# StepperDriver.net
KiCad netlist of a schematic drawn in EAGLE
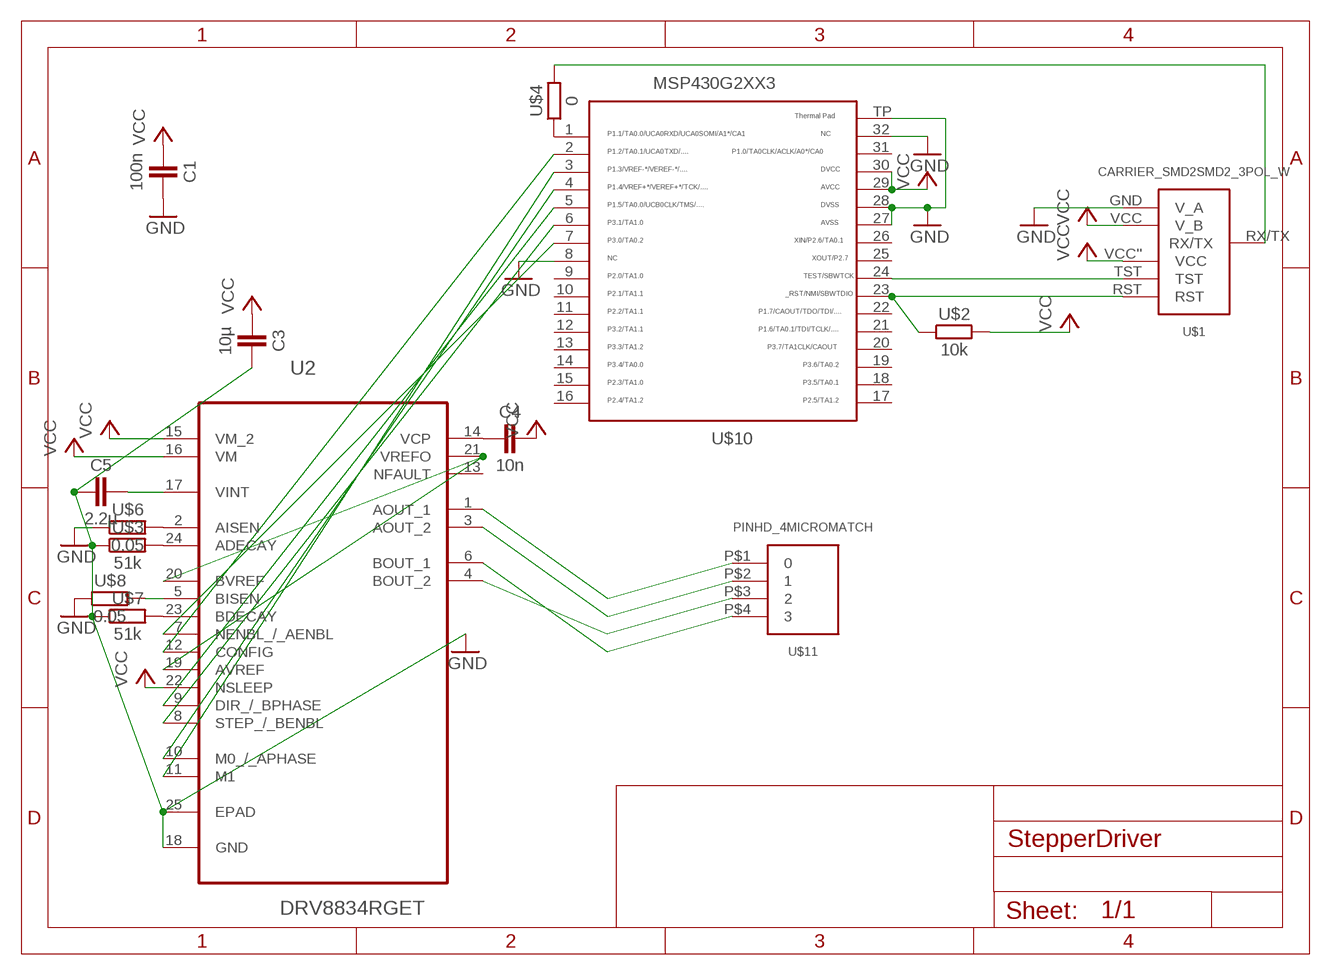
[diagram p0: schematic, sheet 1]

(export (version "E")
  (design (tool "Eeschema 10.0.6"))
  (components
    (comp (ref "C1")
      (value "100n")
      (footprint "eagle-import:603")
      (libsource (lib "eagle-import") (part "CAPACITOR"))
    )
    (comp (ref "C3")
      (value "10µ")
      (footprint "eagle-import:603")
      (libsource (lib "eagle-import") (part "CAPACITOR"))
    )
    (comp (ref "C4")
      (value "10n")
      (footprint "eagle-import:603")
      (libsource (lib "eagle-import") (part "CAPACITOR"))
    )
    (comp (ref "C5")
      (value "2.2µ")
      (footprint "eagle-import:603")
      (libsource (lib "eagle-import") (part "CAPACITOR"))
    )
    (comp (ref "U$1")
      (value "CARRIER_SMD2SMD2_3POL_W")
      (footprint "eagle-import:CARRIER_SMD2_WIDE_3POL")
      (libsource (lib "eagle-import") (part "CARRIER_SMD2SMD2_3POL_W"))
    )
    (comp (ref "U$2")
      (value "10k")
      (footprint "eagle-import:603")
      (libsource (lib "eagle-import") (part "RESISTOR0603"))
    )
    (comp (ref "U$3")
      (value "51k")
      (footprint "eagle-import:603")
      (libsource (lib "eagle-import") (part "RESISTOR0603"))
    )
    (comp (ref "U$4")
      (value "0")
      (footprint "eagle-import:603")
      (libsource (lib "eagle-import") (part "RESISTOR0603"))
    )
    (comp (ref "U$6")
      (value "0.05")
      (footprint "eagle-import:603")
      (libsource (lib "eagle-import") (part "RESISTOR0603"))
    )
    (comp (ref "U$7")
      (value "51k")
      (footprint "eagle-import:603")
      (libsource (lib "eagle-import") (part "RESISTOR0603"))
    )
    (comp (ref "U$8")
      (value "0.05")
      (footprint "eagle-import:603")
      (libsource (lib "eagle-import") (part "RESISTOR0603"))
    )
    (comp (ref "U$10")
      (value "MSP430G2553")
      (footprint "eagle-import:QFN32")
      (libsource (lib "eagle-import") (part "MSP430G2553"))
    )
    (comp (ref "U$11")
      (value "PINHD_4MICROMATCH")
      (footprint "eagle-import:MICROMATCH4P0L")
      (libsource (lib "eagle-import") (part "PINHD_4MICROMATCH"))
    )
    (comp (ref "U2")
      (value "DRV8834RGET")
      (footprint "eagle-import:QFN50P400X400X100-25N")
      (libsource (lib "eagle-import") (part "DRV8834RGET"))
    )
  )
  (nets
    (net (code "1") (name "GND") (class "Default")
      (node (ref "C1") (pin "2") (pinfunction "2_2") (pintype "passive"))
      (node (ref "C3") (pin "2") (pinfunction "2_2") (pintype "passive"))
      (node (ref "C5") (pin "1") (pinfunction "1_1") (pintype "passive"))
      (node (ref "U$1") (pin "GND") (pinfunction "V_A_GND") (pintype "bidirectional"))
      (node (ref "U$10") (pin "27") (pinfunction "27_27") (pintype "bidirectional"))
      (node (ref "U$10") (pin "28") (pinfunction "28_28") (pintype "bidirectional"))
      (node (ref "U$10") (pin "32") (pinfunction "32_32") (pintype "bidirectional"))
      (node (ref "U$10") (pin "8") (pinfunction "8_8") (pintype "bidirectional"))
      (node (ref "U$10") (pin "TP") (pinfunction "TP_TP") (pintype "bidirectional"))
      (node (ref "U$3") (pin "1") (pinfunction "1_1") (pintype "passive"))
      (node (ref "U$6") (pin "1") (pinfunction "1_1") (pintype "passive"))
      (node (ref "U$7") (pin "1") (pinfunction "1_1") (pintype "passive"))
      (node (ref "U$8") (pin "1") (pinfunction "1_1") (pintype "passive"))
      (node (ref "U2") (pin "18") (pinfunction "GND_18") (pintype "passive"))
      (node (ref "U2") (pin "25") (pinfunction "EPAD_25") (pintype "passive"))
    )
    (net (code "2") (name "Net-(U$1-PadRST)") (class "Default")
      (node (ref "U$1") (pin "RST") (pinfunction "RST_RST") (pintype "bidirectional"))
      (node (ref "U$10") (pin "23") (pinfunction "23_23") (pintype "bidirectional"))
      (node (ref "U$2") (pin "1") (pinfunction "1_1") (pintype "passive"))
    )
    (net (code "3") (name "Net-(U$1-PadRX{slash}TX)") (class "Default")
      (node (ref "U$1") (pin "RX/TX") (pinfunction "RX/TX_RX/TX") (pintype "bidirectional"))
      (node (ref "U$4") (pin "2") (pinfunction "2_2") (pintype "passive"))
    )
    (net (code "4") (name "Net-(U$1-PadTST)") (class "Default")
      (node (ref "U$1") (pin "TST") (pinfunction "TST_TST") (pintype "bidirectional"))
      (node (ref "U$10") (pin "24") (pinfunction "24_24") (pintype "bidirectional"))
    )
    (net (code "5") (name "Net-(U$10-Pad1)") (class "Default")
      (node (ref "U$10") (pin "1") (pinfunction "1_1") (pintype "bidirectional"))
      (node (ref "U$4") (pin "1") (pinfunction "1_1") (pintype "passive"))
    )
    (net (code "6") (name "Net-(U$11-0)") (class "Default")
      (node (ref "U$11") (pin "P$1") (pinfunction "0_P$1") (pintype "bidirectional"))
      (node (ref "U2") (pin "1") (pinfunction "AOUT_1_1") (pintype "output"))
    )
    (net (code "7") (name "Net-(U$11-1)") (class "Default")
      (node (ref "U$11") (pin "P$2") (pinfunction "1_P$2") (pintype "bidirectional"))
      (node (ref "U2") (pin "3") (pinfunction "AOUT_2_3") (pintype "output"))
    )
    (net (code "8") (name "Net-(U$11-2)") (class "Default")
      (node (ref "U$11") (pin "P$3") (pinfunction "2_P$3") (pintype "bidirectional"))
      (node (ref "U2") (pin "4") (pinfunction "BOUT_2_4") (pintype "output"))
    )
    (net (code "9") (name "Net-(U$11-3)") (class "Default")
      (node (ref "U$11") (pin "P$4") (pinfunction "3_P$4") (pintype "bidirectional"))
      (node (ref "U2") (pin "6") (pinfunction "BOUT_1_6") (pintype "output"))
    )
    (net (code "10") (name "Net-(U2-ADECAY)") (class "Default")
      (node (ref "U$3") (pin "2") (pinfunction "2_2") (pintype "passive"))
      (node (ref "U2") (pin "24") (pinfunction "ADECAY_24") (pintype "input"))
    )
    (net (code "11") (name "Net-(U2-AISEN)") (class "Default")
      (node (ref "U$6") (pin "2") (pinfunction "2_2") (pintype "passive"))
      (node (ref "U2") (pin "2") (pinfunction "AISEN_2") (pintype "bidirectional"))
    )
    (net (code "12") (name "Net-(U2-AVREF)") (class "Default")
      (node (ref "U2") (pin "19") (pinfunction "AVREF_19") (pintype "input"))
      (node (ref "U2") (pin "20") (pinfunction "BVREF_20") (pintype "input"))
      (node (ref "U2") (pin "21") (pinfunction "VREFO_21") (pintype "output"))
    )
    (net (code "13") (name "Net-(U2-BDECAY)") (class "Default")
      (node (ref "U$7") (pin "2") (pinfunction "2_2") (pintype "passive"))
      (node (ref "U2") (pin "23") (pinfunction "BDECAY_23") (pintype "input"))
    )
    (net (code "14") (name "Net-(U2-BISEN)") (class "Default")
      (node (ref "U$8") (pin "2") (pinfunction "2_2") (pintype "passive"))
      (node (ref "U2") (pin "5") (pinfunction "BISEN_5") (pintype "bidirectional"))
    )
    (net (code "15") (name "Net-(U2-CONFIG)") (class "Default")
      (node (ref "U$10") (pin "2") (pinfunction "2_2") (pintype "bidirectional"))
      (node (ref "U2") (pin "12") (pinfunction "CONFIG_12") (pintype "input"))
    )
    (net (code "16") (name "Net-(U2-DIR_{slash}_BPHASE)") (class "Default")
      (node (ref "U$10") (pin "5") (pinfunction "5_5") (pintype "bidirectional"))
      (node (ref "U2") (pin "9") (pinfunction "DIR_/_BPHASE_9") (pintype "input"))
    )
    (net (code "17") (name "Net-(U2-M0_{slash}_APHASE)") (class "Default")
      (node (ref "U$10") (pin "4") (pinfunction "4_4") (pintype "bidirectional"))
      (node (ref "U2") (pin "10") (pinfunction "M0_/_APHASE_10") (pintype "input"))
    )
    (net (code "18") (name "Net-(U2-M1)") (class "Default")
      (node (ref "U$10") (pin "3") (pinfunction "3_3") (pintype "bidirectional"))
      (node (ref "U2") (pin "11") (pinfunction "M1_11") (pintype "input"))
    )
    (net (code "19") (name "Net-(U2-NENBL_{slash}_AENBL)") (class "Default")
      (node (ref "U$10") (pin "7") (pinfunction "7_7") (pintype "bidirectional"))
      (node (ref "U2") (pin "7") (pinfunction "NENBL_/_AENBL_7") (pintype "input"))
    )
    (net (code "20") (name "Net-(U2-STEP_{slash}_BENBL)") (class "Default")
      (node (ref "U$10") (pin "6") (pinfunction "6_6") (pintype "bidirectional"))
      (node (ref "U2") (pin "8") (pinfunction "STEP_/_BENBL_8") (pintype "input"))
    )
    (net (code "21") (name "Net-(U2-VCP)") (class "Default")
      (node (ref "C4") (pin "1") (pinfunction "1_1") (pintype "passive"))
      (node (ref "U2") (pin "14") (pinfunction "VCP_14") (pintype "output"))
    )
    (net (code "22") (name "Net-(U2-VINT)") (class "Default")
      (node (ref "C5") (pin "2") (pinfunction "2_2") (pintype "passive"))
      (node (ref "U2") (pin "17") (pinfunction "VINT_17") (pintype "power_in"))
    )
    (net (code "23") (name "VCC") (class "Default")
      (node (ref "C1") (pin "1") (pinfunction "1_1") (pintype "passive"))
      (node (ref "C3") (pin "1") (pinfunction "1_1") (pintype "passive"))
      (node (ref "C4") (pin "2") (pinfunction "2_2") (pintype "passive"))
      (node (ref "U$1") (pin "VCC") (pinfunction "V_B_VCC") (pintype "bidirectional"))
      (node (ref "U$1") (pin "VCC''") (pinfunction "VCC_VCC''") (pintype "bidirectional"))
      (node (ref "U$10") (pin "29") (pinfunction "29_29") (pintype "bidirectional"))
      (node (ref "U$10") (pin "30") (pinfunction "30_30") (pintype "bidirectional"))
      (node (ref "U$2") (pin "2") (pinfunction "2_2") (pintype "passive"))
      (node (ref "U2") (pin "15") (pinfunction "VM_2_15") (pintype "power_in"))
      (node (ref "U2") (pin "16") (pinfunction "VM_16") (pintype "power_in"))
      (node (ref "U2") (pin "22") (pinfunction "NSLEEP_22") (pintype "input"))
    )
    (net (code "24") (name "unconnected-(U$10-Pad9)") (class "Default")
      (node (ref "U$10") (pin "9") (pinfunction "9_9") (pintype "bidirectional"))
    )
    (net (code "25") (name "unconnected-(U$10-Pad10)") (class "Default")
      (node (ref "U$10") (pin "10") (pinfunction "10_10") (pintype "bidirectional"))
    )
    (net (code "26") (name "unconnected-(U$10-Pad11)") (class "Default")
      (node (ref "U$10") (pin "11") (pinfunction "11_11") (pintype "bidirectional"))
    )
    (net (code "27") (name "unconnected-(U$10-Pad12)") (class "Default")
      (node (ref "U$10") (pin "12") (pinfunction "12_12") (pintype "bidirectional"))
    )
    (net (code "28") (name "unconnected-(U$10-Pad13)") (class "Default")
      (node (ref "U$10") (pin "13") (pinfunction "13_13") (pintype "bidirectional"))
    )
    (net (code "29") (name "unconnected-(U$10-Pad14)") (class "Default")
      (node (ref "U$10") (pin "14") (pinfunction "14_14") (pintype "bidirectional"))
    )
    (net (code "30") (name "unconnected-(U$10-Pad15)") (class "Default")
      (node (ref "U$10") (pin "15") (pinfunction "15_15") (pintype "bidirectional"))
    )
    (net (code "31") (name "unconnected-(U$10-Pad16)") (class "Default")
      (node (ref "U$10") (pin "16") (pinfunction "16_16") (pintype "bidirectional"))
    )
    (net (code "32") (name "unconnected-(U$10-Pad17)") (class "Default")
      (node (ref "U$10") (pin "17") (pinfunction "17_17") (pintype "bidirectional"))
    )
    (net (code "33") (name "unconnected-(U$10-Pad18)") (class "Default")
      (node (ref "U$10") (pin "18") (pinfunction "18_18") (pintype "bidirectional"))
    )
    (net (code "34") (name "unconnected-(U$10-Pad19)") (class "Default")
      (node (ref "U$10") (pin "19") (pinfunction "19_19") (pintype "bidirectional"))
    )
    (net (code "35") (name "unconnected-(U$10-Pad20)") (class "Default")
      (node (ref "U$10") (pin "20") (pinfunction "20_20") (pintype "bidirectional"))
    )
    (net (code "36") (name "unconnected-(U$10-Pad21)") (class "Default")
      (node (ref "U$10") (pin "21") (pinfunction "21_21") (pintype "bidirectional"))
    )
    (net (code "37") (name "unconnected-(U$10-Pad22)") (class "Default")
      (node (ref "U$10") (pin "22") (pinfunction "22_22") (pintype "bidirectional"))
    )
    (net (code "38") (name "unconnected-(U$10-Pad25)") (class "Default")
      (node (ref "U$10") (pin "25") (pinfunction "25_25") (pintype "bidirectional"))
    )
    (net (code "39") (name "unconnected-(U$10-Pad26)") (class "Default")
      (node (ref "U$10") (pin "26") (pinfunction "26_26") (pintype "bidirectional"))
    )
    (net (code "40") (name "unconnected-(U$10-Pad31)") (class "Default")
      (node (ref "U$10") (pin "31") (pinfunction "31_31") (pintype "bidirectional"))
    )
    (net (code "41") (name "unconnected-(U2-NFAULT-Pad13)") (class "Default")
      (node (ref "U2") (pin "13") (pinfunction "NFAULT_13") (pintype "output"))
    )
  )
)
